# MT7687_Breakout.net
KiCad netlist of a schematic drawn in EAGLE
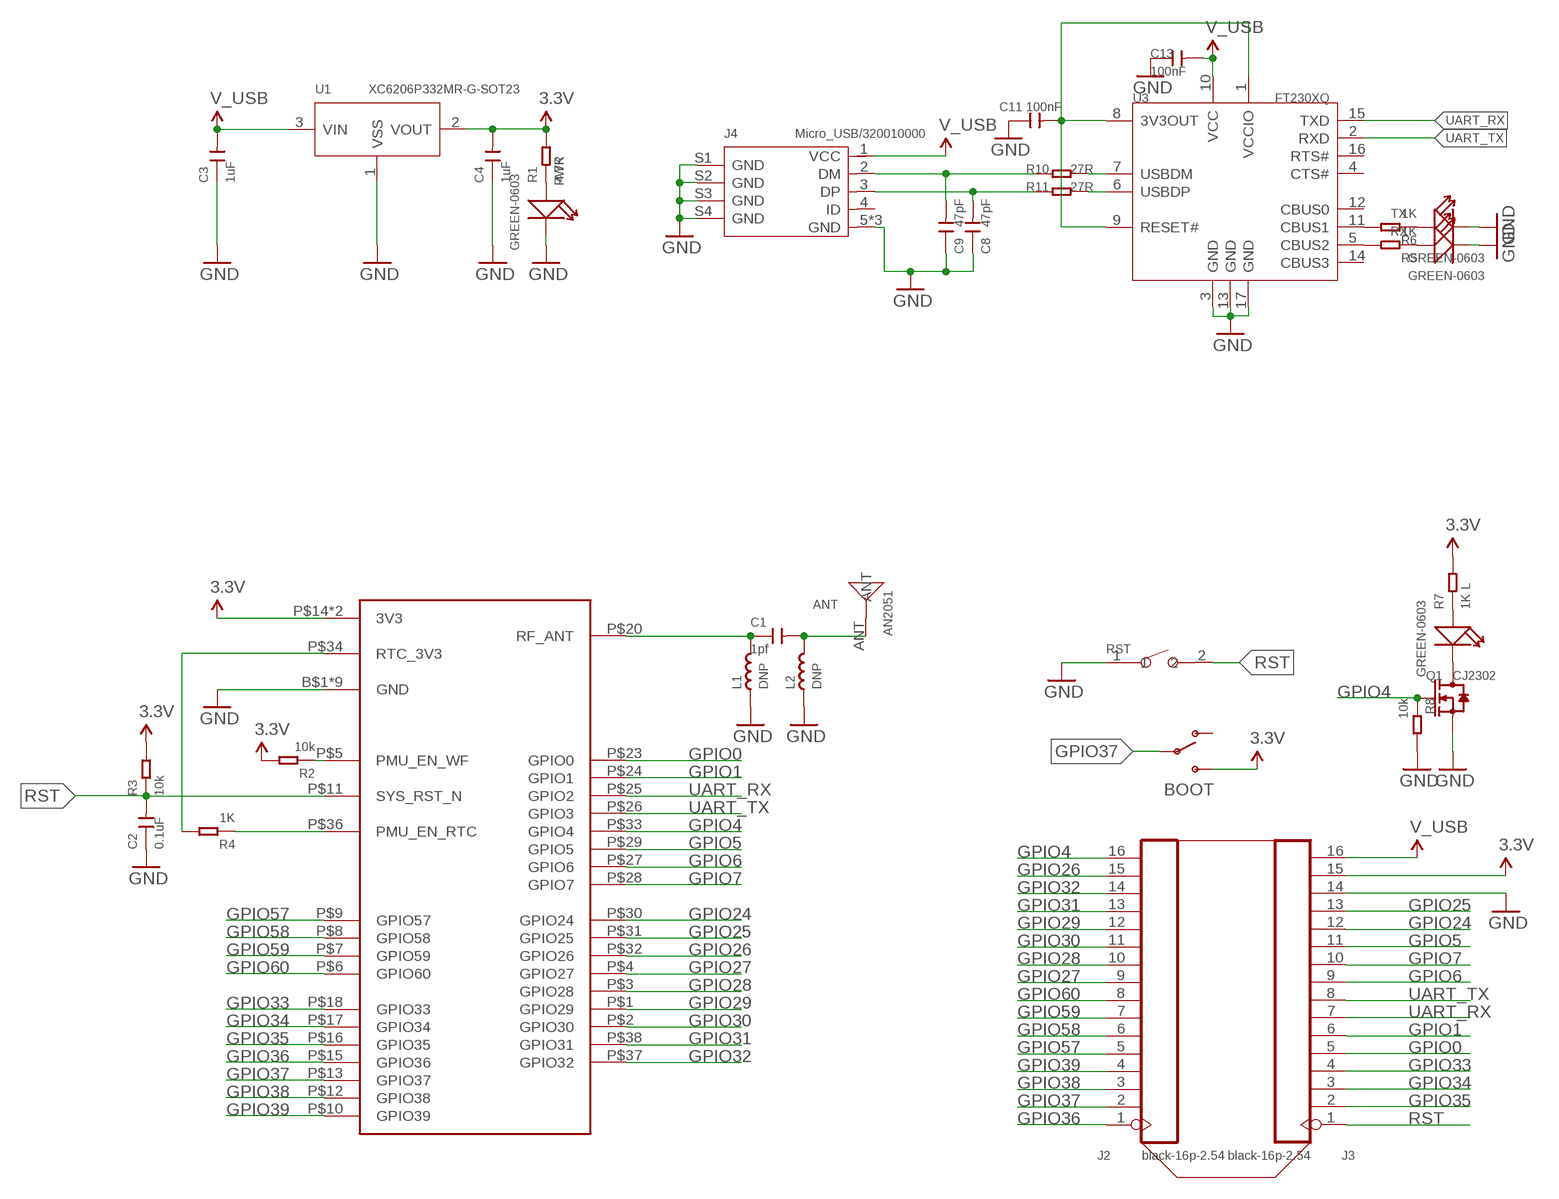
[diagram p0: schematic, sheet 1]

(export (version "E")
  (design (tool "Eeschema 10.0.6"))
  (components
    (comp (ref "ANT")
      (value "AN2051")
      (footprint "eagle-import:ANT-SMD2P-5.05X2X1.07MM")
      (libsource (lib "eagle-import") (part "ANTENNA-AN2051-2.4G"))
    )
    (comp (ref "BOOT")
      (value "SWITCH-SPDTSMD")
      (footprint "eagle-import:AYZ0202")
      (libsource (lib "eagle-import") (part "SWITCH-SPDTSMD"))
    )
    (comp (ref "C1")
      (value "1pf")
      (footprint "eagle-import:C0402")
      (fields (field (name "MPN") "CC0402BRNPO9BN1R0"))
      (libsource (lib "eagle-import") (part "CERAMIC-1PF-50V-0.1PF-NPO(0402)"))
    )
    (comp (ref "C2")
      (value "0.1uF")
      (footprint "eagle-import:C0402")
      (libsource (lib "eagle-import") (part "CAP-0402"))
    )
    (comp (ref "C3")
      (value "1uF")
      (footprint "eagle-import:C0402")
      (libsource (lib "eagle-import") (part "CAP-0402"))
    )
    (comp (ref "C4")
      (value "1uF")
      (footprint "eagle-import:C0402")
      (libsource (lib "eagle-import") (part "CAP-0402"))
    )
    (comp (ref "C8")
      (value "47pF")
      (footprint "eagle-import:C0402")
      (libsource (lib "eagle-import") (part "Discrete-new_CAP-0402"))
    )
    (comp (ref "C9")
      (value "47pF")
      (footprint "eagle-import:C0402")
      (libsource (lib "eagle-import") (part "Discrete-new_CAP-0402"))
    )
    (comp (ref "C11")
      (value "100nF")
      (footprint "eagle-import:C0402")
      (libsource (lib "eagle-import") (part "Discrete-new_CAP-0402"))
    )
    (comp (ref "C13")
      (value "100nF")
      (footprint "eagle-import:C0402")
      (libsource (lib "eagle-import") (part "Discrete-new_CAP-0402"))
    )
    (comp (ref "J2")
      (value "black-16p-2.54")
      (footprint "eagle-import:H16-2.54")
      (fields (field (name "MPN") "F185-1116A0BSYA1"))
      (libsource (lib "eagle-import") (part "DIP-BLACK-FEMALE-HEADER-VERT(16P-2.54)"))
    )
    (comp (ref "J3")
      (value "black-16p-2.54")
      (footprint "eagle-import:H16-2.54")
      (fields (field (name "MPN") "F185-1116A0BSYA1"))
      (libsource (lib "eagle-import") (part "DIP-BLACK-FEMALE-HEADER-VERT(16P-2.54)"))
    )
    (comp (ref "J4")
      (value "Micro_USB/320010000")
      (footprint "eagle-import:5+4P-SMD-0.65-B")
      (libsource (lib "eagle-import") (part "USB-MICRO-5P'5+4P'"))
    )
    (comp (ref "L")
      (value "GREEN-0603")
      (footprint "eagle-import:LED-0603")
      (fields (field (name "MPN") "19-217-G7C-AN1P2-3T"))
      (libsource (lib "eagle-import") (part "SMD-LED-CLEAR-GREEN(0603)"))
    )
    (comp (ref "L1")
      (value "DNP")
      (footprint "eagle-import:L0402")
      (libsource (lib "eagle-import") (part "INDUCTOR/FERRITE-BEAD'0402'"))
    )
    (comp (ref "L2")
      (value "DNP")
      (footprint "eagle-import:L0402")
      (libsource (lib "eagle-import") (part "INDUCTOR/FERRITE-BEAD'0402'"))
    )
    (comp (ref "PWR")
      (value "GREEN-0603")
      (footprint "eagle-import:LED-0603")
      (fields (field (name "MPN") "19-217-G7C-AN1P2-3T"))
      (libsource (lib "eagle-import") (part "SMD-LED-CLEAR-GREEN(0603)"))
    )
    (comp (ref "Q1")
      (value "CJ2302")
      (footprint "eagle-import:SOT-23")
      (libsource (lib "eagle-import") (part "SMD-MOSFET-N-CH-20V-2.1A-CJ2302(SOT-23)"))
    )
    (comp (ref "R1")
      (value "4.7K")
      (footprint "eagle-import:R0402")
      (libsource (lib "eagle-import") (part "Seeed-OPL-Resistor_RES-0402"))
    )
    (comp (ref "R2")
      (value "10k")
      (footprint "eagle-import:R0402")
      (libsource (lib "eagle-import") (part "Seeed-OPL-Resistor_RES-0402"))
    )
    (comp (ref "R3")
      (value "10k")
      (footprint "eagle-import:R0402")
      (libsource (lib "eagle-import") (part "Seeed-OPL-Resistor_RES-0402"))
    )
    (comp (ref "R4")
      (value "1K")
      (footprint "eagle-import:R0402")
      (libsource (lib "eagle-import") (part "Seeed-OPL-Resistor_RES-0402"))
    )
    (comp (ref "R5")
      (value "1K")
      (footprint "eagle-import:R0402")
      (libsource (lib "eagle-import") (part "Seeed-OPL-Resistor_RES-0402"))
    )
    (comp (ref "R6")
      (value "1K")
      (footprint "eagle-import:R0402")
      (libsource (lib "eagle-import") (part "Seeed-OPL-Resistor_RES-0402"))
    )
    (comp (ref "R7")
      (value "1K")
      (footprint "eagle-import:R0402")
      (libsource (lib "eagle-import") (part "Seeed-OPL-Resistor_RES-0402"))
    )
    (comp (ref "R8")
      (value "10k")
      (footprint "eagle-import:R0402")
      (libsource (lib "eagle-import") (part "Seeed-OPL-Resistor_RES-0402"))
    )
    (comp (ref "R10")
      (value "27R")
      (footprint "eagle-import:R0402")
      (libsource (lib "eagle-import") (part "RES-0402"))
    )
    (comp (ref "R11")
      (value "27R")
      (footprint "eagle-import:R0402")
      (libsource (lib "eagle-import") (part "RES-0402"))
    )
    (comp (ref "RST")
      (value "SMD-BUTTON(2P-6.0X3.0X2.5MM)-DHT-1163S")
      (footprint "eagle-import:SW2-4.0-6.0X3.0X2.5MM")
      (libsource (lib "eagle-import") (part "SMD-BUTTON(2P-6.0X3.0X2.5MM)-DHT-1163S"))
    )
    (comp (ref "RX")
      (value "GREEN-0603")
      (footprint "eagle-import:LED-0603")
      (fields (field (name "MPN") "19-217-G7C-AN1P2-3T"))
      (libsource (lib "eagle-import") (part "SMD-LED-CLEAR-GREEN(0603)"))
    )
    (comp (ref "TX")
      (value "GREEN-0603")
      (footprint "eagle-import:LED-0603")
      (fields (field (name "MPN") "19-217-G7C-AN1P2-3T"))
      (libsource (lib "eagle-import") (part "SMD-LED-CLEAR-GREEN(0603)"))
    )
    (comp (ref "U$1")
      (value "MT7687")
      (footprint "eagle-import:MT7687")
      (libsource (lib "eagle-import") (part "MT7687"))
    )
    (comp (ref "U1")
      (value "XC6206P332MR-G-SOT23")
      (footprint "eagle-import:SOT-23")
      (fields (field (name "MPN") "XC6206P332MR-G"))
      (libsource (lib "eagle-import") (part "PMIC-LDO-XC6206P332MR-G(SOT23)"))
    )
    (comp (ref "U3")
      (value "FT230XQ")
      (footprint "eagle-import:QFN-16")
      (libsource (lib "eagle-import") (part "FT230XQ"))
    )
  )
  (nets
    (net (code "1") (name "/GPIO0") (class "Default")
      (node (ref "J3") (pin "5") (pinfunction "5_5") (pintype "passive"))
      (node (ref "U$1") (pin "P$23") (pinfunction "GPIO0_P$23") (pintype "bidirectional"))
    )
    (net (code "2") (name "/GPIO1") (class "Default")
      (node (ref "J3") (pin "6") (pinfunction "6_6") (pintype "passive"))
      (node (ref "U$1") (pin "P$24") (pinfunction "GPIO1_P$24") (pintype "bidirectional"))
    )
    (net (code "3") (name "/GPIO4") (class "Default")
      (node (ref "J2") (pin "16") (pinfunction "16_16") (pintype "passive"))
      (node (ref "Q1") (pin "1") (pinfunction "G_1") (pintype "passive"))
      (node (ref "R8") (pin "1") (pinfunction "1_1") (pintype "passive"))
      (node (ref "U$1") (pin "P$33") (pinfunction "GPIO4_P$33") (pintype "bidirectional"))
    )
    (net (code "4") (name "/GPIO5") (class "Default")
      (node (ref "J3") (pin "11") (pinfunction "11_11") (pintype "passive"))
      (node (ref "U$1") (pin "P$29") (pinfunction "GPIO5_P$29") (pintype "bidirectional"))
    )
    (net (code "5") (name "/GPIO6") (class "Default")
      (node (ref "J3") (pin "9") (pinfunction "9_9") (pintype "passive"))
      (node (ref "U$1") (pin "P$27") (pinfunction "GPIO6_P$27") (pintype "bidirectional"))
    )
    (net (code "6") (name "/GPIO7") (class "Default")
      (node (ref "J3") (pin "10") (pinfunction "10_10") (pintype "passive"))
      (node (ref "U$1") (pin "P$28") (pinfunction "GPIO7_P$28") (pintype "bidirectional"))
    )
    (net (code "7") (name "/GPIO24") (class "Default")
      (node (ref "J3") (pin "12") (pinfunction "12_12") (pintype "passive"))
      (node (ref "U$1") (pin "P$30") (pinfunction "GPIO24_P$30") (pintype "bidirectional"))
    )
    (net (code "8") (name "/GPIO25") (class "Default")
      (node (ref "J3") (pin "13") (pinfunction "13_13") (pintype "passive"))
      (node (ref "U$1") (pin "P$31") (pinfunction "GPIO25_P$31") (pintype "bidirectional"))
    )
    (net (code "9") (name "/GPIO26") (class "Default")
      (node (ref "J2") (pin "15") (pinfunction "15_15") (pintype "passive"))
      (node (ref "U$1") (pin "P$32") (pinfunction "GPIO26_P$32") (pintype "bidirectional"))
    )
    (net (code "10") (name "/GPIO27") (class "Default")
      (node (ref "J2") (pin "9") (pinfunction "9_9") (pintype "passive"))
      (node (ref "U$1") (pin "P$4") (pinfunction "GPIO27_P$4") (pintype "bidirectional"))
    )
    (net (code "11") (name "/GPIO28") (class "Default")
      (node (ref "J2") (pin "10") (pinfunction "10_10") (pintype "passive"))
      (node (ref "U$1") (pin "P$3") (pinfunction "GPIO28_P$3") (pintype "bidirectional"))
    )
    (net (code "12") (name "/GPIO29") (class "Default")
      (node (ref "J2") (pin "12") (pinfunction "12_12") (pintype "passive"))
      (node (ref "U$1") (pin "P$1") (pinfunction "GPIO29_P$1") (pintype "bidirectional"))
    )
    (net (code "13") (name "/GPIO30") (class "Default")
      (node (ref "J2") (pin "11") (pinfunction "11_11") (pintype "passive"))
      (node (ref "U$1") (pin "P$2") (pinfunction "GPIO30_P$2") (pintype "bidirectional"))
    )
    (net (code "14") (name "/GPIO31") (class "Default")
      (node (ref "J2") (pin "13") (pinfunction "13_13") (pintype "passive"))
      (node (ref "U$1") (pin "P$38") (pinfunction "GPIO31_P$38") (pintype "bidirectional"))
    )
    (net (code "15") (name "/GPIO32") (class "Default")
      (node (ref "J2") (pin "14") (pinfunction "14_14") (pintype "passive"))
      (node (ref "U$1") (pin "P$37") (pinfunction "GPIO32_P$37") (pintype "bidirectional"))
    )
    (net (code "16") (name "/GPIO33") (class "Default")
      (node (ref "J3") (pin "4") (pinfunction "4_4") (pintype "passive"))
      (node (ref "U$1") (pin "P$18") (pinfunction "GPIO33_P$18") (pintype "bidirectional"))
    )
    (net (code "17") (name "/GPIO34") (class "Default")
      (node (ref "J3") (pin "3") (pinfunction "3_3") (pintype "passive"))
      (node (ref "U$1") (pin "P$17") (pinfunction "GPIO34_P$17") (pintype "bidirectional"))
    )
    (net (code "18") (name "/GPIO35") (class "Default")
      (node (ref "J3") (pin "2") (pinfunction "2_2") (pintype "passive"))
      (node (ref "U$1") (pin "P$16") (pinfunction "GPIO35_P$16") (pintype "bidirectional"))
    )
    (net (code "19") (name "/GPIO36") (class "Default")
      (node (ref "J2") (pin "1") (pinfunction "1_1") (pintype "passive"))
      (node (ref "U$1") (pin "P$15") (pinfunction "GPIO36_P$15") (pintype "bidirectional"))
    )
    (net (code "20") (name "/GPIO38") (class "Default")
      (node (ref "J2") (pin "3") (pinfunction "3_3") (pintype "passive"))
      (node (ref "U$1") (pin "P$12") (pinfunction "GPIO38_P$12") (pintype "bidirectional"))
    )
    (net (code "21") (name "/GPIO39") (class "Default")
      (node (ref "J2") (pin "4") (pinfunction "4_4") (pintype "passive"))
      (node (ref "U$1") (pin "P$10") (pinfunction "GPIO39_P$10") (pintype "bidirectional"))
    )
    (net (code "22") (name "/GPIO57") (class "Default")
      (node (ref "J2") (pin "5") (pinfunction "5_5") (pintype "passive"))
      (node (ref "U$1") (pin "P$9") (pinfunction "GPIO57_P$9") (pintype "bidirectional"))
    )
    (net (code "23") (name "/GPIO58") (class "Default")
      (node (ref "J2") (pin "6") (pinfunction "6_6") (pintype "passive"))
      (node (ref "U$1") (pin "P$8") (pinfunction "GPIO58_P$8") (pintype "bidirectional"))
    )
    (net (code "24") (name "/GPIO59") (class "Default")
      (node (ref "J2") (pin "7") (pinfunction "7_7") (pintype "passive"))
      (node (ref "U$1") (pin "P$7") (pinfunction "GPIO59_P$7") (pintype "bidirectional"))
    )
    (net (code "25") (name "/GPIO60") (class "Default")
      (node (ref "J2") (pin "8") (pinfunction "8_8") (pintype "passive"))
      (node (ref "U$1") (pin "P$6") (pinfunction "GPIO60_P$6") (pintype "bidirectional"))
    )
    (net (code "26") (name "3.3V") (class "Default")
      (node (ref "BOOT") (pin "3") (pinfunction "S_3") (pintype "passive"))
      (node (ref "C4") (pin "2") (pinfunction "2_2") (pintype "passive"))
      (node (ref "J3") (pin "15") (pinfunction "15_15") (pintype "passive"))
      (node (ref "R1") (pin "2") (pinfunction "2_2") (pintype "passive"))
      (node (ref "R2") (pin "2") (pinfunction "2_2") (pintype "passive"))
      (node (ref "R3") (pin "2") (pinfunction "2_2") (pintype "passive"))
      (node (ref "R7") (pin "2") (pinfunction "2_2") (pintype "passive"))
      (node (ref "U$1") (pin "P$14") (pinfunction "3V3_P$14") (pintype "bidirectional"))
      (node (ref "U$1") (pin "P$39") (pinfunction "3V3_P$39") (pintype "bidirectional"))
      (node (ref "U1") (pin "2") (pinfunction "VOUT_2") (pintype "output"))
    )
    (net (code "27") (name "GND") (class "Default")
      (node (ref "C11") (pin "1") (pinfunction "1_1") (pintype "passive"))
      (node (ref "C13") (pin "1") (pinfunction "1_1") (pintype "passive"))
      (node (ref "C2") (pin "1") (pinfunction "1_1") (pintype "passive"))
      (node (ref "C3") (pin "1") (pinfunction "1_1") (pintype "passive"))
      (node (ref "C4") (pin "1") (pinfunction "1_1") (pintype "passive"))
      (node (ref "C8") (pin "1") (pinfunction "1_1") (pintype "passive"))
      (node (ref "C9") (pin "1") (pinfunction "1_1") (pintype "passive"))
      (node (ref "J3") (pin "14") (pinfunction "14_14") (pintype "passive"))
      (node (ref "J4") (pin "5") (pinfunction "GND_5") (pintype "bidirectional"))
      (node (ref "J4") (pin "S1") (pinfunction "GND_S1") (pintype "bidirectional"))
      (node (ref "J4") (pin "S2") (pinfunction "GND_S2") (pintype "bidirectional"))
      (node (ref "J4") (pin "S3") (pinfunction "GND_S3") (pintype "bidirectional"))
      (node (ref "J4") (pin "S4") (pinfunction "GND_S4") (pintype "bidirectional"))
      (node (ref "J4") (pin "S5") (pinfunction "GND_S5") (pintype "bidirectional"))
      (node (ref "J4") (pin "S6") (pinfunction "GND_S6") (pintype "bidirectional"))
      (node (ref "L1") (pin "1") (pinfunction "1_1") (pintype "passive"))
      (node (ref "L2") (pin "1") (pinfunction "1_1") (pintype "passive"))
      (node (ref "PWR") (pin "-") (pinfunction "-_-") (pintype "passive"))
      (node (ref "Q1") (pin "2") (pinfunction "S_2") (pintype "passive"))
      (node (ref "R8") (pin "2") (pinfunction "2_2") (pintype "passive"))
      (node (ref "RST") (pin "1") (pinfunction "1_1") (pintype "bidirectional"))
      (node (ref "RX") (pin "-") (pinfunction "-_-") (pintype "passive"))
      (node (ref "TX") (pin "-") (pinfunction "-_-") (pintype "passive"))
      (node (ref "U$1") (pin "B$1") (pinfunction "GND_B$1") (pintype "bidirectional"))
      (node (ref "U$1") (pin "B$2") (pinfunction "GND_B$2") (pintype "bidirectional"))
      (node (ref "U$1") (pin "B$3") (pinfunction "GND_B$3") (pintype "bidirectional"))
      (node (ref "U$1") (pin "B$4") (pinfunction "GND_B$4") (pintype "bidirectional"))
      (node (ref "U$1") (pin "P$19") (pinfunction "GND_P$19") (pintype "bidirectional"))
      (node (ref "U$1") (pin "P$21") (pinfunction "GND_P$21") (pintype "bidirectional"))
      (node (ref "U$1") (pin "P$22") (pinfunction "GND_P$22") (pintype "bidirectional"))
      (node (ref "U$1") (pin "P$35") (pinfunction "GND_P$35") (pintype "bidirectional"))
      (node (ref "U$1") (pin "P$40") (pinfunction "GND_P$40") (pintype "bidirectional"))
      (node (ref "U1") (pin "1") (pinfunction "VSS_1") (pintype "power_in"))
      (node (ref "U3") (pin "13") (pinfunction "GND_13") (pintype "bidirectional"))
      (node (ref "U3") (pin "17") (pinfunction "GND_17") (pintype "bidirectional"))
      (node (ref "U3") (pin "3") (pinfunction "GND_3") (pintype "bidirectional"))
    )
    (net (code "28") (name "GPIO37") (class "Default")
      (node (ref "BOOT") (pin "2") (pinfunction "P_2") (pintype "passive"))
      (node (ref "J2") (pin "2") (pinfunction "2_2") (pintype "passive"))
      (node (ref "U$1") (pin "P$13") (pinfunction "GPIO37_P$13") (pintype "bidirectional"))
    )
    (net (code "29") (name "Net-(ANT-PadANT)") (class "Default")
      (node (ref "ANT") (pin "ANT") (pinfunction "ANT_ANT") (pintype "bidirectional"))
      (node (ref "C1") (pin "2") (pinfunction "2_2") (pintype "passive"))
      (node (ref "L2") (pin "2") (pinfunction "2_2") (pintype "passive"))
    )
    (net (code "30") (name "Net-(J4-DM)") (class "Default")
      (node (ref "C9") (pin "2") (pinfunction "2_2") (pintype "passive"))
      (node (ref "J4") (pin "2") (pinfunction "DM_2") (pintype "bidirectional"))
      (node (ref "R10") (pin "1") (pinfunction "1_1") (pintype "passive"))
    )
    (net (code "31") (name "Net-(J4-DP)") (class "Default")
      (node (ref "C8") (pin "2") (pinfunction "2_2") (pintype "passive"))
      (node (ref "J4") (pin "3") (pinfunction "DP_3") (pintype "bidirectional"))
      (node (ref "R11") (pin "1") (pinfunction "1_1") (pintype "passive"))
    )
    (net (code "32") (name "Net-(L-Pad+)") (class "Default")
      (node (ref "L") (pin "+") (pinfunction "+_+") (pintype "passive"))
      (node (ref "R7") (pin "1") (pinfunction "1_1") (pintype "passive"))
    )
    (net (code "33") (name "Net-(PWR-Pad+)") (class "Default")
      (node (ref "PWR") (pin "+") (pinfunction "+_+") (pintype "passive"))
      (node (ref "R1") (pin "1") (pinfunction "1_1") (pintype "passive"))
    )
    (net (code "34") (name "Net-(Q1-D)") (class "Default")
      (node (ref "L") (pin "-") (pinfunction "-_-") (pintype "passive"))
      (node (ref "Q1") (pin "3") (pinfunction "D_3") (pintype "passive"))
    )
    (net (code "35") (name "Net-(R5-Pad1)") (class "Default")
      (node (ref "R5") (pin "1") (pinfunction "1_1") (pintype "passive"))
      (node (ref "RX") (pin "+") (pinfunction "+_+") (pintype "passive"))
    )
    (net (code "36") (name "Net-(R6-Pad1)") (class "Default")
      (node (ref "R6") (pin "1") (pinfunction "1_1") (pintype "passive"))
      (node (ref "TX") (pin "+") (pinfunction "+_+") (pintype "passive"))
    )
    (net (code "37") (name "Net-(U$1-PMU_EN_RTC)") (class "Default")
      (node (ref "R4") (pin "1") (pinfunction "1_1") (pintype "passive"))
      (node (ref "U$1") (pin "P$36") (pinfunction "PMU_EN_RTC_P$36") (pintype "bidirectional"))
    )
    (net (code "38") (name "Net-(U$1-PMU_EN_WF)") (class "Default")
      (node (ref "R2") (pin "1") (pinfunction "1_1") (pintype "passive"))
      (node (ref "U$1") (pin "P$5") (pinfunction "PMU_EN_WF_P$5") (pintype "bidirectional"))
    )
    (net (code "39") (name "Net-(U$1-RF_ANT)") (class "Default")
      (node (ref "C1") (pin "1") (pinfunction "1_1") (pintype "passive"))
      (node (ref "L1") (pin "2") (pinfunction "2_2") (pintype "passive"))
      (node (ref "U$1") (pin "P$20") (pinfunction "RF_ANT_P$20") (pintype "bidirectional"))
    )
    (net (code "40") (name "Net-(U$1-RTC_3V3)") (class "Default")
      (node (ref "R4") (pin "2") (pinfunction "2_2") (pintype "passive"))
      (node (ref "U$1") (pin "P$34") (pinfunction "RTC_3V3_P$34") (pintype "bidirectional"))
    )
    (net (code "41") (name "Net-(U3-3V3OUT)") (class "Default")
      (node (ref "C11") (pin "2") (pinfunction "2_2") (pintype "passive"))
      (node (ref "U3") (pin "1") (pinfunction "VCCIO_1") (pintype "bidirectional"))
      (node (ref "U3") (pin "8") (pinfunction "3V3OUT_8") (pintype "bidirectional"))
      (node (ref "U3") (pin "9") (pinfunction "RESET#_9") (pintype "bidirectional"))
    )
    (net (code "42") (name "Net-(U3-CBUS1)") (class "Default")
      (node (ref "R6") (pin "2") (pinfunction "2_2") (pintype "passive"))
      (node (ref "U3") (pin "11") (pinfunction "CBUS1_11") (pintype "bidirectional"))
    )
    (net (code "43") (name "Net-(U3-CBUS2)") (class "Default")
      (node (ref "R5") (pin "2") (pinfunction "2_2") (pintype "passive"))
      (node (ref "U3") (pin "5") (pinfunction "CBUS2_5") (pintype "bidirectional"))
    )
    (net (code "44") (name "Net-(U3-USBDM)") (class "Default")
      (node (ref "R10") (pin "2") (pinfunction "2_2") (pintype "passive"))
      (node (ref "U3") (pin "7") (pinfunction "USBDM_7") (pintype "bidirectional"))
    )
    (net (code "45") (name "Net-(U3-USBDP)") (class "Default")
      (node (ref "R11") (pin "2") (pinfunction "2_2") (pintype "passive"))
      (node (ref "U3") (pin "6") (pinfunction "USBDP_6") (pintype "bidirectional"))
    )
    (net (code "46") (name "RST") (class "Default")
      (node (ref "C2") (pin "2") (pinfunction "2_2") (pintype "passive"))
      (node (ref "J3") (pin "1") (pinfunction "1_1") (pintype "passive"))
      (node (ref "R3") (pin "1") (pinfunction "1_1") (pintype "passive"))
      (node (ref "RST") (pin "2") (pinfunction "2_2") (pintype "bidirectional"))
      (node (ref "U$1") (pin "P$11") (pinfunction "SYS_RST_N_P$11") (pintype "bidirectional"))
    )
    (net (code "47") (name "UART_RX") (class "Default")
      (node (ref "J3") (pin "7") (pinfunction "7_7") (pintype "passive"))
      (node (ref "U$1") (pin "P$25") (pinfunction "GPIO2_P$25") (pintype "bidirectional"))
      (node (ref "U3") (pin "15") (pinfunction "TXD_15") (pintype "bidirectional"))
    )
    (net (code "48") (name "UART_TX") (class "Default")
      (node (ref "J3") (pin "8") (pinfunction "8_8") (pintype "passive"))
      (node (ref "U$1") (pin "P$26") (pinfunction "GPIO3_P$26") (pintype "bidirectional"))
      (node (ref "U3") (pin "2") (pinfunction "RXD_2") (pintype "bidirectional"))
    )
    (net (code "49") (name "V_USB") (class "Default")
      (node (ref "C13") (pin "2") (pinfunction "2_2") (pintype "passive"))
      (node (ref "C3") (pin "2") (pinfunction "2_2") (pintype "passive"))
      (node (ref "J3") (pin "16") (pinfunction "16_16") (pintype "passive"))
      (node (ref "J4") (pin "1") (pinfunction "VCC_1") (pintype "bidirectional"))
      (node (ref "U1") (pin "3") (pinfunction "VIN_3") (pintype "input"))
      (node (ref "U3") (pin "10") (pinfunction "VCC_10") (pintype "bidirectional"))
    )
    (net (code "50") (name "unconnected-(BOOT-O-Pad1)") (class "Default")
      (node (ref "BOOT") (pin "1") (pinfunction "O_1") (pintype "passive"))
    )
    (net (code "51") (name "unconnected-(J4-ID-Pad4)") (class "Default")
      (node (ref "J4") (pin "4") (pinfunction "ID_4") (pintype "bidirectional"))
    )
    (net (code "52") (name "unconnected-(U3-CBUS0-Pad12)") (class "Default")
      (node (ref "U3") (pin "12") (pinfunction "CBUS0_12") (pintype "bidirectional"))
    )
    (net (code "53") (name "unconnected-(U3-CBUS3-Pad14)") (class "Default")
      (node (ref "U3") (pin "14") (pinfunction "CBUS3_14") (pintype "bidirectional"))
    )
    (net (code "54") (name "unconnected-(U3-CTS#-Pad4)") (class "Default")
      (node (ref "U3") (pin "4") (pinfunction "CTS#_4") (pintype "bidirectional"))
    )
    (net (code "55") (name "unconnected-(U3-RTS#-Pad16)") (class "Default")
      (node (ref "U3") (pin "16") (pinfunction "RTS#_16") (pintype "bidirectional"))
    )
  )
)
